# Tds_NonSmd.net
KiCad netlist of a schematic drawn in EAGLE
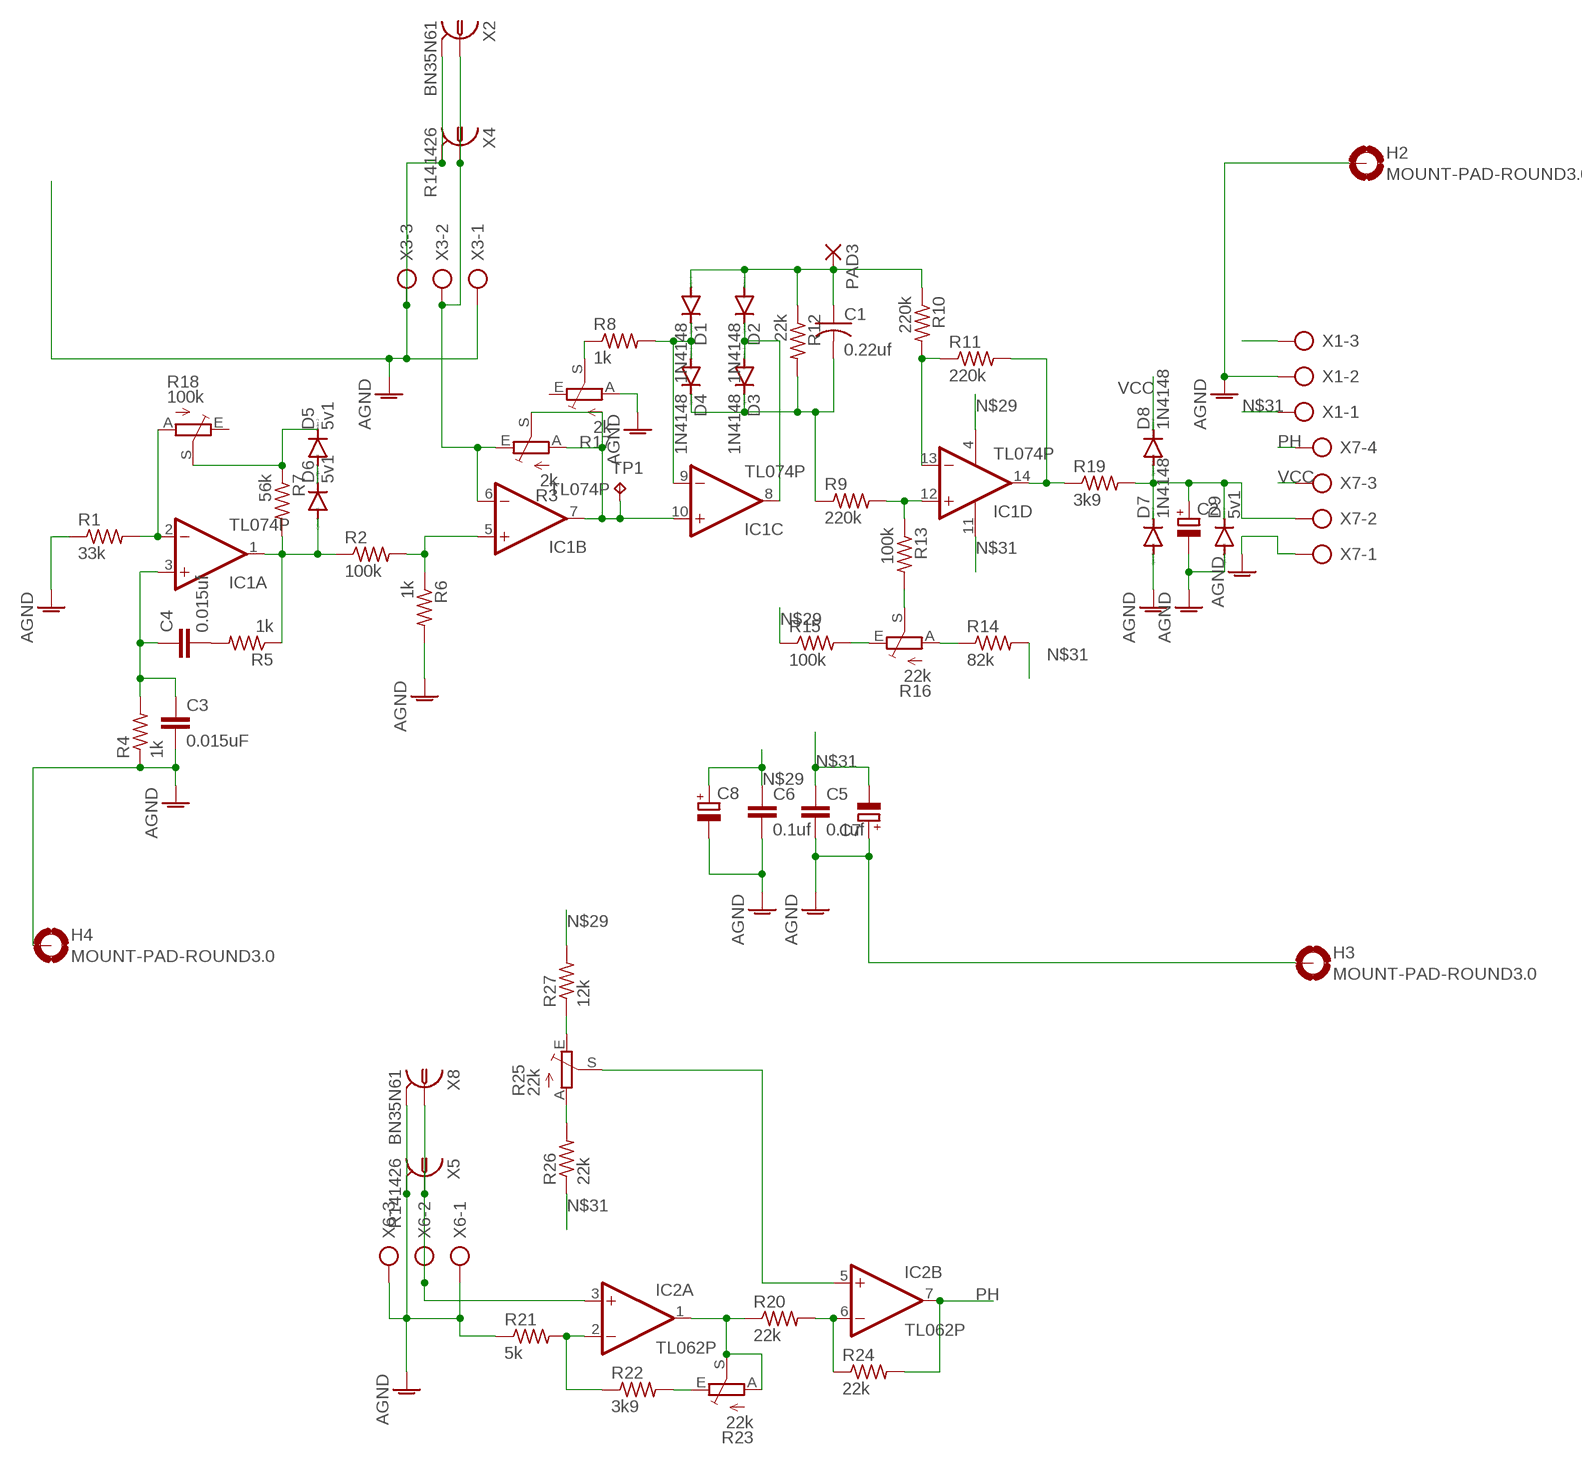
[diagram p0: schematic, sheet 1]

(export (version "E")
  (design (tool "Eeschema 10.0.6"))
  (components
    (comp (ref "C1")
      (value "0.22uf")
      (footprint "eagle-import:C050-024X044")
      (libsource (lib "eagle-import") (part "C-US050-024X044"))
    )
    (comp (ref "C2")
      (value "CPOL-EUE5-8.5")
      (footprint "eagle-import:E5-8,5")
      (libsource (lib "eagle-import") (part "CPOL-EUE5-8.5"))
    )
    (comp (ref "C3")
      (value "0.015uF")
      (footprint "eagle-import:C050-024X044")
      (libsource (lib "eagle-import") (part "C-EU050-024X044"))
    )
    (comp (ref "C4")
      (value "0.015uf")
      (footprint "eagle-import:C050-024X044")
      (libsource (lib "eagle-import") (part "C-EU050-024X044"))
    )
    (comp (ref "C5")
      (value "0.1uf")
      (footprint "eagle-import:C5B2.5")
      (libsource (lib "eagle-import") (part "C5/2.5"))
    )
    (comp (ref "C6")
      (value "0.1uf")
      (footprint "eagle-import:C5B2.5")
      (libsource (lib "eagle-import") (part "C5/2.5"))
    )
    (comp (ref "C7")
      (value "CPOL-EUE5-8.5")
      (footprint "eagle-import:E5-8,5")
      (libsource (lib "eagle-import") (part "CPOL-EUE5-8.5"))
    )
    (comp (ref "C8")
      (value "CPOL-EUE5-8.5")
      (footprint "eagle-import:E5-8,5")
      (libsource (lib "eagle-import") (part "CPOL-EUE5-8.5"))
    )
    (comp (ref "D1")
      (value "1N4148")
      (footprint "eagle-import:DO35-7")
      (libsource (lib "eagle-import") (part "1N4148DO35-7"))
    )
    (comp (ref "D2")
      (value "1N4148")
      (footprint "eagle-import:DO35-7")
      (libsource (lib "eagle-import") (part "1N4148DO35-7"))
    )
    (comp (ref "D3")
      (value "1N4148")
      (footprint "eagle-import:DO35-7")
      (libsource (lib "eagle-import") (part "1N4148DO35-7"))
    )
    (comp (ref "D4")
      (value "1N4148")
      (footprint "eagle-import:DO35-7")
      (libsource (lib "eagle-import") (part "1N4148DO35-7"))
    )
    (comp (ref "D5")
      (value "5v1")
      (footprint "eagle-import:DO35-7")
      (libsource (lib "eagle-import") (part "1N4148DO35-7"))
    )
    (comp (ref "D6")
      (value "5v1")
      (footprint "eagle-import:DO35-7")
      (libsource (lib "eagle-import") (part "1N4148DO35-7"))
    )
    (comp (ref "D7")
      (value "1N4148")
      (footprint "eagle-import:DO35-7")
      (libsource (lib "eagle-import") (part "1N4148DO35-7"))
    )
    (comp (ref "D8")
      (value "1N4148")
      (footprint "eagle-import:DO35-7")
      (libsource (lib "eagle-import") (part "1N4148DO35-7"))
    )
    (comp (ref "D9")
      (value "5v1")
      (footprint "eagle-import:DO35-7")
      (libsource (lib "eagle-import") (part "1N4148DO35-7"))
    )
    (comp (ref "H2")
      (value "MOUNT-PAD-ROUND3.0")
      (footprint "eagle-import:3,0-PAD")
      (libsource (lib "eagle-import") (part "MOUNT-PAD-ROUND3.0"))
    )
    (comp (ref "H3")
      (value "MOUNT-PAD-ROUND3.0")
      (footprint "eagle-import:3,0-PAD")
      (libsource (lib "eagle-import") (part "MOUNT-PAD-ROUND3.0"))
    )
    (comp (ref "H4")
      (value "MOUNT-PAD-ROUND3.0")
      (footprint "eagle-import:3,0-PAD")
      (libsource (lib "eagle-import") (part "MOUNT-PAD-ROUND3.0"))
    )
    (comp (ref "IC1")
      (value "TL074P")
      (footprint "eagle-import:DIL14")
      (libsource (lib "eagle-import") (part "TL074P"))
    )
    (comp (ref "IC2")
      (value "TL062P")
      (footprint "eagle-import:DIL08")
      (libsource (lib "eagle-import") (part "TL062P"))
    )
    (comp (ref "PAD3")
      (value "2,54/1,1")
      (footprint "eagle-import:2,54_1,1")
      (libsource (lib "eagle-import") (part "2,54/1,1"))
    )
    (comp (ref "R1")
      (value "33k")
      (footprint "eagle-import:0207_7")
      (libsource (lib "eagle-import") (part "resistor_348_R-US_0207/7"))
    )
    (comp (ref "R2")
      (value "100k")
      (footprint "eagle-import:0207_10")
      (libsource (lib "eagle-import") (part "R-US_0207/10"))
    )
    (comp (ref "R3")
      (value "2k")
      (footprint "eagle-import:S64W")
      (libsource (lib "eagle-import") (part "TRIM_EU-S64W"))
    )
    (comp (ref "R4")
      (value "1k")
      (footprint "eagle-import:0207_7")
      (libsource (lib "eagle-import") (part "resistor_348_R-US_0207/7"))
    )
    (comp (ref "R5")
      (value "1k")
      (footprint "eagle-import:0207_7")
      (libsource (lib "eagle-import") (part "resistor_348_R-US_0207/7"))
    )
    (comp (ref "R6")
      (value "1k")
      (footprint "eagle-import:0207_7")
      (libsource (lib "eagle-import") (part "resistor_348_R-US_0207/7"))
    )
    (comp (ref "R7")
      (value "56k")
      (footprint "eagle-import:0207_7")
      (libsource (lib "eagle-import") (part "resistor_348_R-US_0207/7"))
    )
    (comp (ref "R8")
      (value "1k")
      (footprint "eagle-import:0207_7")
      (libsource (lib "eagle-import") (part "resistor_348_R-US_0207/7"))
    )
    (comp (ref "R9")
      (value "220k")
      (footprint "eagle-import:0207_7")
      (libsource (lib "eagle-import") (part "resistor_348_R-US_0207/7"))
    )
    (comp (ref "R10")
      (value "220k")
      (footprint "eagle-import:0207_7")
      (libsource (lib "eagle-import") (part "resistor_348_R-US_0207/7"))
    )
    (comp (ref "R11")
      (value "220k")
      (footprint "eagle-import:0207_7")
      (libsource (lib "eagle-import") (part "resistor_348_R-US_0207/7"))
    )
    (comp (ref "R12")
      (value "22k")
      (footprint "eagle-import:0207_7")
      (libsource (lib "eagle-import") (part "resistor_348_R-US_0207/7"))
    )
    (comp (ref "R13")
      (value "100k")
      (footprint "eagle-import:0207_7")
      (libsource (lib "eagle-import") (part "resistor_348_R-US_0207/7"))
    )
    (comp (ref "R14")
      (value "82k")
      (footprint "eagle-import:0207_7")
      (libsource (lib "eagle-import") (part "resistor_348_R-US_0207/7"))
    )
    (comp (ref "R15")
      (value "100k")
      (footprint "eagle-import:0207_7")
      (libsource (lib "eagle-import") (part "resistor_348_R-US_0207/7"))
    )
    (comp (ref "R16")
      (value "22k")
      (footprint "eagle-import:S64W")
      (libsource (lib "eagle-import") (part "TRIM_EU-S64W"))
    )
    (comp (ref "R17")
      (value "2k")
      (footprint "eagle-import:S64W")
      (libsource (lib "eagle-import") (part "TRIM_EU-S64W"))
    )
    (comp (ref "R18")
      (value "100k")
      (footprint "eagle-import:S64W")
      (libsource (lib "eagle-import") (part "TRIM_EU-S64W"))
    )
    (comp (ref "R19")
      (value "3k9")
      (footprint "eagle-import:0207_7")
      (libsource (lib "eagle-import") (part "resistor_348_R-US_0207/7"))
    )
    (comp (ref "R20")
      (value "22k")
      (footprint "eagle-import:0207_7")
      (libsource (lib "eagle-import") (part "resistor_348_R-US_0207/7"))
    )
    (comp (ref "R21")
      (value "5k")
      (footprint "eagle-import:0207_7")
      (libsource (lib "eagle-import") (part "resistor_348_R-US_0207/7"))
    )
    (comp (ref "R22")
      (value "3k9")
      (footprint "eagle-import:0207_7")
      (libsource (lib "eagle-import") (part "resistor_348_R-US_0207/7"))
    )
    (comp (ref "R23")
      (value "22k")
      (footprint "eagle-import:S64W")
      (libsource (lib "eagle-import") (part "TRIM_EU-S64W"))
    )
    (comp (ref "R24")
      (value "22k")
      (footprint "eagle-import:0207_7")
      (libsource (lib "eagle-import") (part "resistor_348_R-US_0207/7"))
    )
    (comp (ref "R25")
      (value "22k")
      (footprint "eagle-import:S64W")
      (libsource (lib "eagle-import") (part "TRIM_EU-S64W"))
    )
    (comp (ref "R26")
      (value "22k")
      (footprint "eagle-import:0207_7")
      (libsource (lib "eagle-import") (part "resistor_348_R-US_0207/7"))
    )
    (comp (ref "R27")
      (value "12k")
      (footprint "eagle-import:0207_7")
      (libsource (lib "eagle-import") (part "resistor_348_R-US_0207/7"))
    )
    (comp (ref "TP1")
      (value "TPPAD1-13")
      (footprint "eagle-import:P1-13")
      (libsource (lib "eagle-import") (part "TPPAD1-13"))
    )
    (comp (ref "X1")
      (value "AK500/3")
      (footprint "eagle-import:AK500_3")
      (libsource (lib "eagle-import") (part "AK500/3"))
    )
    (comp (ref "X2")
      (value "BN35N61")
      (footprint "eagle-import:B35N61")
      (libsource (lib "eagle-import") (part "BN35N61"))
    )
    (comp (ref "X3")
      (value "AK500/3")
      (footprint "eagle-import:AK500_3")
      (libsource (lib "eagle-import") (part "AK500/3"))
    )
    (comp (ref "X4")
      (value "R141426")
      (footprint "eagle-import:R141426")
      (fields (field (name "MF") "FARNELL") (field (name "MPN") "R141426161"))
      (libsource (lib "eagle-import") (part "R141426"))
    )
    (comp (ref "X5")
      (value "R141426")
      (footprint "eagle-import:R141426")
      (fields (field (name "MF") "FARNELL") (field (name "MPN") "R141426161"))
      (libsource (lib "eagle-import") (part "R141426"))
    )
    (comp (ref "X6")
      (value "AK500/3")
      (footprint "eagle-import:AK500_3")
      (libsource (lib "eagle-import") (part "AK500/3"))
    )
    (comp (ref "X7")
      (value "AK500/4")
      (footprint "eagle-import:AK500_4")
      (libsource (lib "eagle-import") (part "AK500/4"))
    )
    (comp (ref "X8")
      (value "BN35N61")
      (footprint "eagle-import:B35N61")
      (libsource (lib "eagle-import") (part "BN35N61"))
    )
  )
  (nets
    (net (code "1") (name "/N$29") (class "Default")
      (node (ref "C6") (pin "1") (pinfunction "1_1") (pintype "passive"))
      (node (ref "C8") (pin "+") (pinfunction "+_+") (pintype "passive"))
      (node (ref "IC1") (pin "4") (pinfunction "V+_4") (pintype "power_in"))
      (node (ref "R15") (pin "1") (pinfunction "1_1") (pintype "passive"))
      (node (ref "R27") (pin "2") (pinfunction "2_2") (pintype "passive"))
      (node (ref "X1") (pin "3") (pinfunction "KL_3") (pintype "passive"))
    )
    (net (code "2") (name "/N$31") (class "Default")
      (node (ref "C5") (pin "1") (pinfunction "1_1") (pintype "passive"))
      (node (ref "C7") (pin "-") (pinfunction "-_-") (pintype "passive"))
      (node (ref "IC1") (pin "11") (pinfunction "V-_11") (pintype "power_in"))
      (node (ref "R14") (pin "2") (pinfunction "2_2") (pintype "passive"))
      (node (ref "R26") (pin "1") (pinfunction "1_1") (pintype "passive"))
      (node (ref "X1") (pin "1") (pinfunction "KL_1") (pintype "passive"))
    )
    (net (code "3") (name "/PH") (class "Default")
      (node (ref "IC2") (pin "7") (pinfunction "OUT_7") (pintype "output"))
      (node (ref "R24") (pin "2") (pinfunction "2_2") (pintype "passive"))
      (node (ref "X7") (pin "4") (pinfunction "KL_4") (pintype "passive"))
    )
    (net (code "4") (name "/VCC") (class "Default")
      (node (ref "D8") (pin "C") (pinfunction "C_C") (pintype "passive"))
      (node (ref "X7") (pin "3") (pinfunction "KL_3") (pintype "passive"))
    )
    (net (code "5") (name "AGND") (class "Default")
      (node (ref "C2") (pin "-") (pinfunction "-_-") (pintype "passive"))
      (node (ref "C3") (pin "2") (pinfunction "2_2") (pintype "passive"))
      (node (ref "C5") (pin "2") (pinfunction "2_2") (pintype "passive"))
      (node (ref "C6") (pin "2") (pinfunction "2_2") (pintype "passive"))
      (node (ref "C7") (pin "+") (pinfunction "+_+") (pintype "passive"))
      (node (ref "C8") (pin "-") (pinfunction "-_-") (pintype "passive"))
      (node (ref "D7") (pin "A") (pinfunction "A_A") (pintype "passive"))
      (node (ref "D9") (pin "A") (pinfunction "A_A") (pintype "passive"))
      (node (ref "H2") (pin "B3,0") (pinfunction "MOUNT_B3,0") (pintype "passive"))
      (node (ref "H3") (pin "B3,0") (pinfunction "MOUNT_B3,0") (pintype "passive"))
      (node (ref "H4") (pin "B3,0") (pinfunction "MOUNT_B3,0") (pintype "passive"))
      (node (ref "R1") (pin "1") (pinfunction "1_1") (pintype "passive"))
      (node (ref "R17") (pin "A") (pinfunction "A_A") (pintype "passive"))
      (node (ref "R21") (pin "1") (pinfunction "1_1") (pintype "passive"))
      (node (ref "R4") (pin "1") (pinfunction "1_1") (pintype "passive"))
      (node (ref "R6") (pin "2") (pinfunction "2_2") (pintype "passive"))
      (node (ref "X1") (pin "2") (pinfunction "KL_2") (pintype "passive"))
      (node (ref "X2") (pin "2") (pinfunction "2_2") (pintype "passive"))
      (node (ref "X2") (pin "3") (pinfunction "2_3") (pintype "passive"))
      (node (ref "X2") (pin "4") (pinfunction "2_4") (pintype "passive"))
      (node (ref "X2") (pin "5") (pinfunction "2_5") (pintype "passive"))
      (node (ref "X3") (pin "1") (pinfunction "KL_1") (pintype "passive"))
      (node (ref "X3") (pin "3") (pinfunction "KL_3") (pintype "passive"))
      (node (ref "X4") (pin "2") (pinfunction "2_2") (pintype "passive"))
      (node (ref "X4") (pin "3") (pinfunction "2_3") (pintype "passive"))
      (node (ref "X4") (pin "4") (pinfunction "2_4") (pintype "passive"))
      (node (ref "X4") (pin "5") (pinfunction "2_5") (pintype "passive"))
      (node (ref "X5") (pin "2") (pinfunction "2_2") (pintype "passive"))
      (node (ref "X5") (pin "3") (pinfunction "2_3") (pintype "passive"))
      (node (ref "X5") (pin "4") (pinfunction "2_4") (pintype "passive"))
      (node (ref "X5") (pin "5") (pinfunction "2_5") (pintype "passive"))
      (node (ref "X6") (pin "1") (pinfunction "KL_1") (pintype "passive"))
      (node (ref "X6") (pin "3") (pinfunction "KL_3") (pintype "passive"))
      (node (ref "X7") (pin "1") (pinfunction "KL_1") (pintype "passive"))
      (node (ref "X8") (pin "2") (pinfunction "2_2") (pintype "passive"))
      (node (ref "X8") (pin "3") (pinfunction "2_3") (pintype "passive"))
      (node (ref "X8") (pin "4") (pinfunction "2_4") (pintype "passive"))
      (node (ref "X8") (pin "5") (pinfunction "2_5") (pintype "passive"))
    )
    (net (code "6") (name "Net-(C1-Pad2)") (class "Default")
      (node (ref "C1") (pin "2") (pinfunction "2_2") (pintype "passive"))
      (node (ref "D3") (pin "C") (pinfunction "C_C") (pintype "passive"))
      (node (ref "D4") (pin "C") (pinfunction "C_C") (pintype "passive"))
      (node (ref "R12") (pin "2") (pinfunction "2_2") (pintype "passive"))
      (node (ref "R9") (pin "1") (pinfunction "1_1") (pintype "passive"))
    )
    (net (code "7") (name "Net-(C4-Pad2)") (class "Default")
      (node (ref "C4") (pin "2") (pinfunction "2_2") (pintype "passive"))
      (node (ref "R5") (pin "2") (pinfunction "2_2") (pintype "passive"))
    )
    (net (code "8") (name "Net-(D5-PadA)") (class "Default")
      (node (ref "D5") (pin "A") (pinfunction "A_A") (pintype "passive"))
      (node (ref "D6") (pin "C") (pinfunction "C_C") (pintype "passive"))
    )
    (net (code "9") (name "Net-(D5-PadC)") (class "Default")
      (node (ref "D5") (pin "C") (pinfunction "C_C") (pintype "passive"))
      (node (ref "R18") (pin "S") (pinfunction "S_S") (pintype "passive"))
      (node (ref "R7") (pin "1") (pinfunction "1_1") (pintype "passive"))
    )
    (net (code "10") (name "Net-(IC1A-+IN)") (class "Default")
      (node (ref "C3") (pin "1") (pinfunction "1_1") (pintype "passive"))
      (node (ref "C4") (pin "1") (pinfunction "1_1") (pintype "passive"))
      (node (ref "IC1") (pin "3") (pinfunction "+IN_3") (pintype "input"))
      (node (ref "R4") (pin "2") (pinfunction "2_2") (pintype "passive"))
    )
    (net (code "11") (name "Net-(IC1A--IN)") (class "Default")
      (node (ref "IC1") (pin "2") (pinfunction "-IN_2") (pintype "input"))
      (node (ref "R1") (pin "2") (pinfunction "2_2") (pintype "passive"))
      (node (ref "R18") (pin "A") (pinfunction "A_A") (pintype "passive"))
    )
    (net (code "12") (name "Net-(IC1A-OUT)") (class "Default")
      (node (ref "D6") (pin "A") (pinfunction "A_A") (pintype "passive"))
      (node (ref "IC1") (pin "1") (pinfunction "OUT_1") (pintype "output"))
      (node (ref "R2") (pin "1") (pinfunction "1_1") (pintype "passive"))
      (node (ref "R5") (pin "1") (pinfunction "1_1") (pintype "passive"))
      (node (ref "R7") (pin "2") (pinfunction "2_2") (pintype "passive"))
    )
    (net (code "13") (name "Net-(IC1B-+IN)") (class "Default")
      (node (ref "IC1") (pin "5") (pinfunction "+IN_5") (pintype "input"))
      (node (ref "R2") (pin "2") (pinfunction "2_2") (pintype "passive"))
      (node (ref "R6") (pin "1") (pinfunction "1_1") (pintype "passive"))
    )
    (net (code "14") (name "Net-(IC1B--IN)") (class "Default")
      (node (ref "IC1") (pin "6") (pinfunction "-IN_6") (pintype "input"))
      (node (ref "R3") (pin "E") (pinfunction "E_E") (pintype "passive"))
      (node (ref "X2") (pin "1") (pinfunction "1_1") (pintype "passive"))
      (node (ref "X3") (pin "2") (pinfunction "KL_2") (pintype "passive"))
      (node (ref "X4") (pin "1") (pinfunction "1_1") (pintype "passive"))
    )
    (net (code "15") (name "Net-(IC1B-OUT)") (class "Default")
      (node (ref "IC1") (pin "10") (pinfunction "+IN_10") (pintype "input"))
      (node (ref "IC1") (pin "7") (pinfunction "OUT_7") (pintype "output"))
      (node (ref "R3") (pin "A") (pinfunction "A_A") (pintype "passive"))
      (node (ref "R3") (pin "S") (pinfunction "S_S") (pintype "passive"))
      (node (ref "TP1") (pin "TP") (pinfunction "TP_TP") (pintype "input"))
    )
    (net (code "16") (name "Net-(IC1C--IN)") (class "Default")
      (node (ref "D1") (pin "C") (pinfunction "C_C") (pintype "passive"))
      (node (ref "D4") (pin "A") (pinfunction "A_A") (pintype "passive"))
      (node (ref "IC1") (pin "9") (pinfunction "-IN_9") (pintype "input"))
      (node (ref "R8") (pin "2") (pinfunction "2_2") (pintype "passive"))
    )
    (net (code "17") (name "Net-(IC1C-OUT)") (class "Default")
      (node (ref "D2") (pin "C") (pinfunction "C_C") (pintype "passive"))
      (node (ref "D3") (pin "A") (pinfunction "A_A") (pintype "passive"))
      (node (ref "IC1") (pin "8") (pinfunction "OUT_8") (pintype "output"))
    )
    (net (code "18") (name "Net-(IC1D-+IN)") (class "Default")
      (node (ref "IC1") (pin "12") (pinfunction "+IN_12") (pintype "input"))
      (node (ref "R13") (pin "1") (pinfunction "1_1") (pintype "passive"))
      (node (ref "R9") (pin "2") (pinfunction "2_2") (pintype "passive"))
    )
    (net (code "19") (name "Net-(IC1D--IN)") (class "Default")
      (node (ref "IC1") (pin "13") (pinfunction "-IN_13") (pintype "input"))
      (node (ref "R10") (pin "2") (pinfunction "2_2") (pintype "passive"))
      (node (ref "R11") (pin "1") (pinfunction "1_1") (pintype "passive"))
    )
    (net (code "20") (name "Net-(IC1D-OUT)") (class "Default")
      (node (ref "IC1") (pin "14") (pinfunction "OUT_14") (pintype "output"))
      (node (ref "R11") (pin "2") (pinfunction "2_2") (pintype "passive"))
      (node (ref "R19") (pin "1") (pinfunction "1_1") (pintype "passive"))
    )
    (net (code "21") (name "Net-(IC2A-+IN)") (class "Default")
      (node (ref "IC2") (pin "3") (pinfunction "+IN_3") (pintype "input"))
      (node (ref "X5") (pin "1") (pinfunction "1_1") (pintype "passive"))
      (node (ref "X6") (pin "2") (pinfunction "KL_2") (pintype "passive"))
      (node (ref "X8") (pin "1") (pinfunction "1_1") (pintype "passive"))
    )
    (net (code "22") (name "Net-(IC2A--IN)") (class "Default")
      (node (ref "IC2") (pin "2") (pinfunction "-IN_2") (pintype "input"))
      (node (ref "R21") (pin "2") (pinfunction "2_2") (pintype "passive"))
      (node (ref "R22") (pin "1") (pinfunction "1_1") (pintype "passive"))
    )
    (net (code "23") (name "Net-(IC2A-OUT)") (class "Default")
      (node (ref "IC2") (pin "1") (pinfunction "OUT_1") (pintype "output"))
      (node (ref "R20") (pin "1") (pinfunction "1_1") (pintype "passive"))
      (node (ref "R23") (pin "A") (pinfunction "A_A") (pintype "passive"))
      (node (ref "R23") (pin "S") (pinfunction "S_S") (pintype "passive"))
    )
    (net (code "24") (name "Net-(IC2B-+IN)") (class "Default")
      (node (ref "IC2") (pin "5") (pinfunction "+IN_5") (pintype "input"))
      (node (ref "R25") (pin "S") (pinfunction "S_S") (pintype "passive"))
    )
    (net (code "25") (name "Net-(IC2B--IN)") (class "Default")
      (node (ref "IC2") (pin "6") (pinfunction "-IN_6") (pintype "input"))
      (node (ref "R20") (pin "2") (pinfunction "2_2") (pintype "passive"))
      (node (ref "R24") (pin "1") (pinfunction "1_1") (pintype "passive"))
    )
    (net (code "26") (name "Net-(PAD3-P)") (class "Default")
      (node (ref "C1") (pin "1") (pinfunction "1_1") (pintype "passive"))
      (node (ref "D1") (pin "A") (pinfunction "A_A") (pintype "passive"))
      (node (ref "D2") (pin "A") (pinfunction "A_A") (pintype "passive"))
      (node (ref "PAD3") (pin "1") (pinfunction "P_1") (pintype "passive"))
      (node (ref "R10") (pin "1") (pinfunction "1_1") (pintype "passive"))
      (node (ref "R12") (pin "1") (pinfunction "1_1") (pintype "passive"))
    )
    (net (code "27") (name "Net-(R13-Pad2)") (class "Default")
      (node (ref "R13") (pin "2") (pinfunction "2_2") (pintype "passive"))
      (node (ref "R16") (pin "S") (pinfunction "S_S") (pintype "passive"))
    )
    (net (code "28") (name "Net-(R14-Pad1)") (class "Default")
      (node (ref "R14") (pin "1") (pinfunction "1_1") (pintype "passive"))
      (node (ref "R16") (pin "A") (pinfunction "A_A") (pintype "passive"))
    )
    (net (code "29") (name "Net-(R15-Pad2)") (class "Default")
      (node (ref "R15") (pin "2") (pinfunction "2_2") (pintype "passive"))
      (node (ref "R16") (pin "E") (pinfunction "E_E") (pintype "passive"))
    )
    (net (code "30") (name "Net-(R17-PadS)") (class "Default")
      (node (ref "R17") (pin "S") (pinfunction "S_S") (pintype "passive"))
      (node (ref "R8") (pin "1") (pinfunction "1_1") (pintype "passive"))
    )
    (net (code "31") (name "Net-(R22-Pad2)") (class "Default")
      (node (ref "R22") (pin "2") (pinfunction "2_2") (pintype "passive"))
      (node (ref "R23") (pin "E") (pinfunction "E_E") (pintype "passive"))
    )
    (net (code "32") (name "Net-(R25-PadA)") (class "Default")
      (node (ref "R25") (pin "A") (pinfunction "A_A") (pintype "passive"))
      (node (ref "R26") (pin "2") (pinfunction "2_2") (pintype "passive"))
    )
    (net (code "33") (name "Net-(R25-PadE)") (class "Default")
      (node (ref "R25") (pin "E") (pinfunction "E_E") (pintype "passive"))
      (node (ref "R27") (pin "1") (pinfunction "1_1") (pintype "passive"))
    )
    (net (code "34") (name "Net-(X7B-KL)") (class "Default")
      (node (ref "C2") (pin "+") (pinfunction "+_+") (pintype "passive"))
      (node (ref "D7") (pin "C") (pinfunction "C_C") (pintype "passive"))
      (node (ref "D8") (pin "A") (pinfunction "A_A") (pintype "passive"))
      (node (ref "D9") (pin "C") (pinfunction "C_C") (pintype "passive"))
      (node (ref "R19") (pin "2") (pinfunction "2_2") (pintype "passive"))
      (node (ref "X7") (pin "2") (pinfunction "KL_2") (pintype "passive"))
    )
    (net (code "35") (name "unconnected-(R17-PadE)") (class "Default")
      (node (ref "R17") (pin "E") (pinfunction "E_E") (pintype "passive"))
    )
    (net (code "36") (name "unconnected-(R18-PadE)") (class "Default")
      (node (ref "R18") (pin "E") (pinfunction "E_E") (pintype "passive"))
    )
  )
)
